# S3_Arduino.net
KiCad netlist of a schematic drawn in Altium Designer
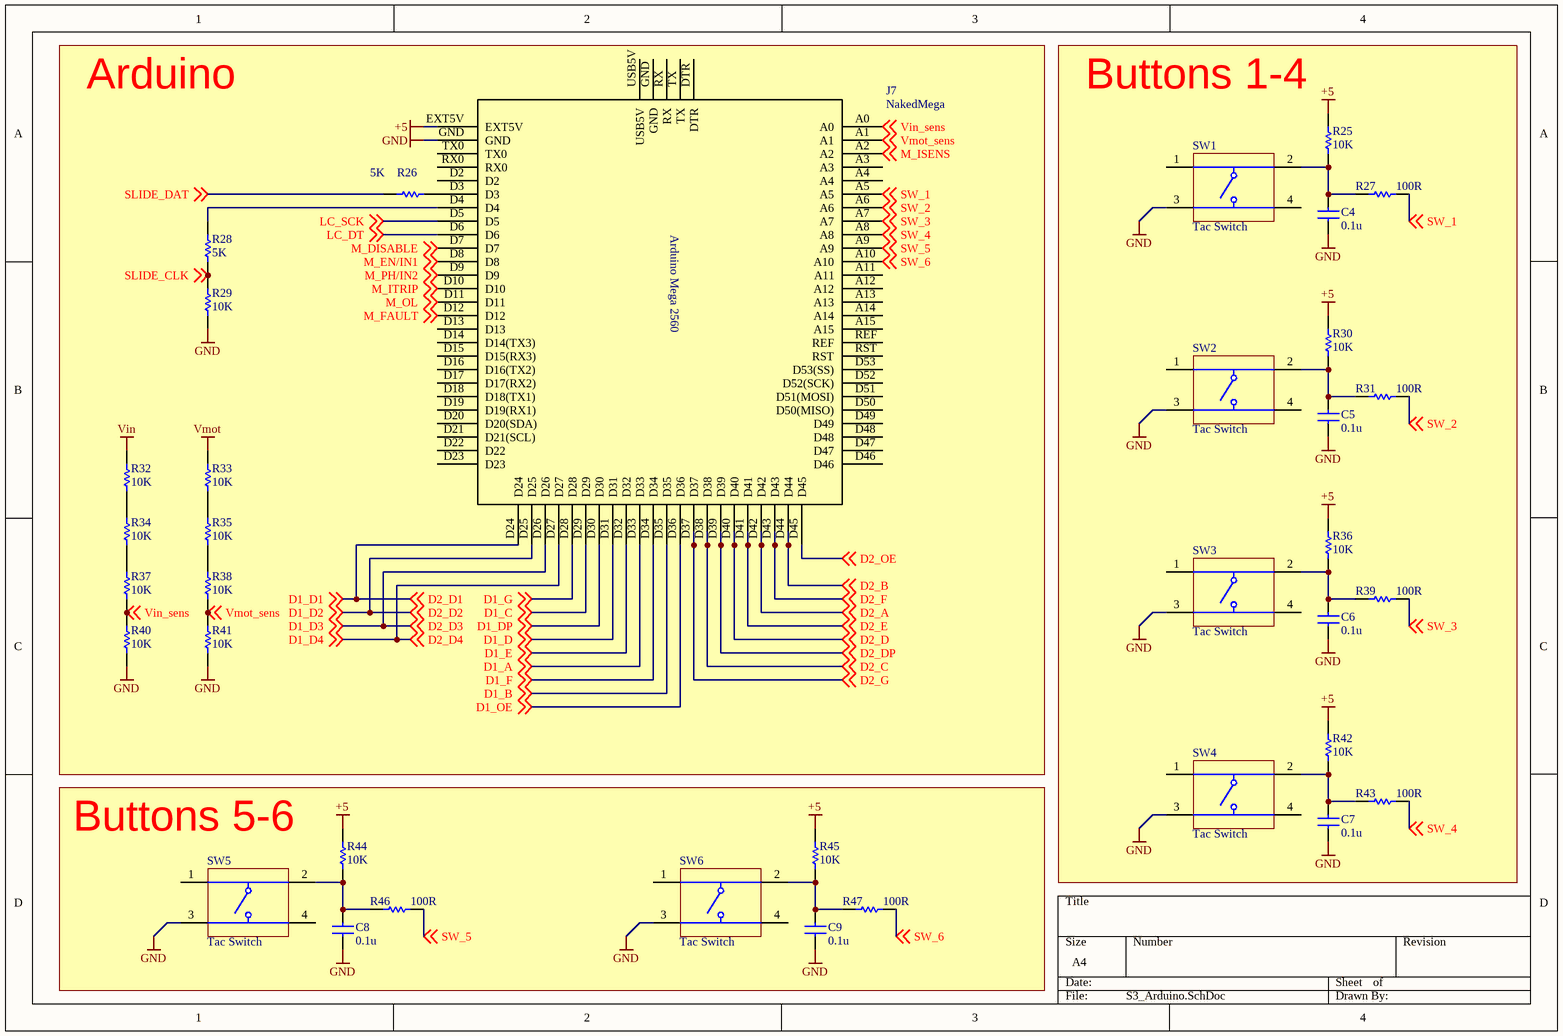
[diagram p0: S3_Arduino.SchDoc]

(export (version "E")
  (design (tool "Eeschema 10.0.6"))
  (components
    (comp (ref "C4")
      (value "0.1u")
      (footprint "Ceramic Cap 5mm")
      (libsource (lib "Res and Cap") (part "Cap"))
    )
    (comp (ref "C5")
      (value "0.1u")
      (footprint "Ceramic Cap 5mm")
      (libsource (lib "Res and Cap") (part "Cap"))
    )
    (comp (ref "C6")
      (value "0.1u")
      (footprint "Ceramic Cap 5mm")
      (libsource (lib "Res and Cap") (part "Cap"))
    )
    (comp (ref "C7")
      (value "0.1u")
      (footprint "Ceramic Cap 5mm")
      (libsource (lib "Res and Cap") (part "Cap"))
    )
    (comp (ref "C8")
      (value "0.1u")
      (footprint "Ceramic Cap 5mm")
      (libsource (lib "Res and Cap") (part "Cap"))
    )
    (comp (ref "C9")
      (value "0.1u")
      (footprint "Ceramic Cap 5mm")
      (libsource (lib "Res and Cap") (part "Cap"))
    )
    (comp (ref "J7")
      (value "NakedMega")
      (footprint "Arduino Mega")
      (libsource (lib "Custom") (part "NakedMega"))
    )
    (comp (ref "R25")
      (value "10K")
      (footprint "AXIAL-0.3-3D")
      (description "Resistor")
      (fields (field (name "Comment") "Res1") (field (name "PUBLISHER") "Altium Limited"))
      (libsource (lib "Miscellaneous Devices") (part "Res1"))
    )
    (comp (ref "R26")
      (value "5K")
      (footprint "AXIAL-0.3-3D")
      (description "Resistor")
      (fields (field (name "Comment") "Res1") (field (name "PUBLISHER") "Altium Limited"))
      (libsource (lib "Miscellaneous Devices") (part "Res1"))
    )
    (comp (ref "R27")
      (value "100R")
      (footprint "AXIAL-0.3-3D")
      (description "Resistor")
      (fields (field (name "Comment") "Res1") (field (name "PUBLISHER") "Altium Limited"))
      (libsource (lib "Miscellaneous Devices") (part "Res1"))
    )
    (comp (ref "R28")
      (value "5K")
      (footprint "AXIAL-0.3-3D")
      (description "Resistor")
      (fields (field (name "Comment") "Res1") (field (name "PUBLISHER") "Altium Limited"))
      (libsource (lib "Miscellaneous Devices") (part "Res1"))
    )
    (comp (ref "R29")
      (value "10K")
      (footprint "AXIAL-0.3-3D")
      (description "Resistor")
      (fields (field (name "Comment") "Res1") (field (name "PUBLISHER") "Altium Limited"))
      (libsource (lib "Miscellaneous Devices") (part "Res1"))
    )
    (comp (ref "R30")
      (value "10K")
      (footprint "AXIAL-0.3-3D")
      (description "Resistor")
      (fields (field (name "Comment") "Res1") (field (name "PUBLISHER") "Altium Limited"))
      (libsource (lib "Miscellaneous Devices") (part "Res1"))
    )
    (comp (ref "R31")
      (value "100R")
      (footprint "AXIAL-0.3-3D")
      (description "Resistor")
      (fields (field (name "Comment") "Res1") (field (name "PUBLISHER") "Altium Limited"))
      (libsource (lib "Miscellaneous Devices") (part "Res1"))
    )
    (comp (ref "R32")
      (value "10K")
      (footprint "AXIAL-0.3-3D")
      (description "Resistor")
      (fields (field (name "Comment") "Res1") (field (name "PUBLISHER") "Altium Limited"))
      (libsource (lib "Miscellaneous Devices") (part "Res1"))
    )
    (comp (ref "R33")
      (value "10K")
      (footprint "AXIAL-0.3-3D")
      (description "Resistor")
      (fields (field (name "Comment") "Res1") (field (name "PUBLISHER") "Altium Limited"))
      (libsource (lib "Miscellaneous Devices") (part "Res1"))
    )
    (comp (ref "R34")
      (value "10K")
      (footprint "AXIAL-0.3-3D")
      (description "Resistor")
      (fields (field (name "Comment") "Res1") (field (name "PUBLISHER") "Altium Limited"))
      (libsource (lib "Miscellaneous Devices") (part "Res1"))
    )
    (comp (ref "R35")
      (value "10K")
      (footprint "AXIAL-0.3-3D")
      (description "Resistor")
      (fields (field (name "Comment") "Res1") (field (name "PUBLISHER") "Altium Limited"))
      (libsource (lib "Miscellaneous Devices") (part "Res1"))
    )
    (comp (ref "R36")
      (value "10K")
      (footprint "AXIAL-0.3-3D")
      (description "Resistor")
      (fields (field (name "Comment") "Res1") (field (name "PUBLISHER") "Altium Limited"))
      (libsource (lib "Miscellaneous Devices") (part "Res1"))
    )
    (comp (ref "R37")
      (value "10K")
      (footprint "AXIAL-0.3-3D")
      (description "Resistor")
      (fields (field (name "Comment") "Res1") (field (name "PUBLISHER") "Altium Limited"))
      (libsource (lib "Miscellaneous Devices") (part "Res1"))
    )
    (comp (ref "R38")
      (value "10K")
      (footprint "AXIAL-0.3-3D")
      (description "Resistor")
      (fields (field (name "Comment") "Res1") (field (name "PUBLISHER") "Altium Limited"))
      (libsource (lib "Miscellaneous Devices") (part "Res1"))
    )
    (comp (ref "R39")
      (value "100R")
      (footprint "AXIAL-0.3-3D")
      (description "Resistor")
      (fields (field (name "Comment") "Res1") (field (name "PUBLISHER") "Altium Limited"))
      (libsource (lib "Miscellaneous Devices") (part "Res1"))
    )
    (comp (ref "R40")
      (value "10K")
      (footprint "AXIAL-0.3-3D")
      (description "Resistor")
      (fields (field (name "Comment") "Res1") (field (name "PUBLISHER") "Altium Limited"))
      (libsource (lib "Miscellaneous Devices") (part "Res1"))
    )
    (comp (ref "R41")
      (value "10K")
      (footprint "AXIAL-0.3-3D")
      (description "Resistor")
      (fields (field (name "Comment") "Res1") (field (name "PUBLISHER") "Altium Limited"))
      (libsource (lib "Miscellaneous Devices") (part "Res1"))
    )
    (comp (ref "R42")
      (value "10K")
      (footprint "AXIAL-0.3-3D")
      (description "Resistor")
      (fields (field (name "Comment") "Res1") (field (name "PUBLISHER") "Altium Limited"))
      (libsource (lib "Miscellaneous Devices") (part "Res1"))
    )
    (comp (ref "R43")
      (value "100R")
      (footprint "AXIAL-0.3-3D")
      (description "Resistor")
      (fields (field (name "Comment") "Res1") (field (name "PUBLISHER") "Altium Limited"))
      (libsource (lib "Miscellaneous Devices") (part "Res1"))
    )
    (comp (ref "R44")
      (value "10K")
      (footprint "AXIAL-0.3-3D")
      (description "Resistor")
      (fields (field (name "Comment") "Res1") (field (name "PUBLISHER") "Altium Limited"))
      (libsource (lib "Miscellaneous Devices") (part "Res1"))
    )
    (comp (ref "R45")
      (value "10K")
      (footprint "AXIAL-0.3-3D")
      (description "Resistor")
      (fields (field (name "Comment") "Res1") (field (name "PUBLISHER") "Altium Limited"))
      (libsource (lib "Miscellaneous Devices") (part "Res1"))
    )
    (comp (ref "R46")
      (value "100R")
      (footprint "AXIAL-0.3-3D")
      (description "Resistor")
      (fields (field (name "Comment") "Res1") (field (name "PUBLISHER") "Altium Limited"))
      (libsource (lib "Miscellaneous Devices") (part "Res1"))
    )
    (comp (ref "R47")
      (value "100R")
      (footprint "AXIAL-0.3-3D")
      (description "Resistor")
      (fields (field (name "Comment") "Res1") (field (name "PUBLISHER") "Altium Limited"))
      (libsource (lib "Miscellaneous Devices") (part "Res1"))
    )
    (comp (ref "SW1")
      (value "Tac Switch")
      (footprint "TacSwitch")
      (libsource (lib "Custom") (part "Tac Switch"))
    )
    (comp (ref "SW2")
      (value "Tac Switch")
      (footprint "TacSwitch")
      (libsource (lib "Custom") (part "Tac Switch"))
    )
    (comp (ref "SW3")
      (value "Tac Switch")
      (footprint "TacSwitch")
      (libsource (lib "Custom") (part "Tac Switch"))
    )
    (comp (ref "SW4")
      (value "Tac Switch")
      (footprint "TacSwitch")
      (libsource (lib "Custom") (part "Tac Switch"))
    )
    (comp (ref "SW5")
      (value "Tac Switch")
      (footprint "TacSwitch")
      (libsource (lib "Custom") (part "Tac Switch"))
    )
    (comp (ref "SW6")
      (value "Tac Switch")
      (footprint "TacSwitch")
      (libsource (lib "Custom") (part "Tac Switch"))
    )
  )
  (nets
    (net (code "1") (name "+5") (class "Default")
      (node (ref "J7") (pin "EXT5V") (pinfunction "EXT5V_EXT5V") (pintype "passive"))
      (node (ref "R25") (pin "1") (pinfunction "1_1") (pintype "passive"))
      (node (ref "R30") (pin "1") (pinfunction "1_1") (pintype "passive"))
      (node (ref "R36") (pin "1") (pinfunction "1_1") (pintype "passive"))
      (node (ref "R42") (pin "1") (pinfunction "1_1") (pintype "passive"))
      (node (ref "R44") (pin "1") (pinfunction "1_1") (pintype "passive"))
      (node (ref "R45") (pin "1") (pinfunction "1_1") (pintype "passive"))
    )
    (net (code "2") (name "D1_A") (class "Default")
      (node (ref "J7") (pin "D33") (pinfunction "D33_D33") (pintype "passive"))
    )
    (net (code "3") (name "D1_B") (class "Default")
      (node (ref "J7") (pin "D35") (pinfunction "D35_D35") (pintype "passive"))
    )
    (net (code "4") (name "D1_C") (class "Default")
      (node (ref "J7") (pin "D29") (pinfunction "D29_D29") (pintype "passive"))
    )
    (net (code "5") (name "D1_D") (class "Default")
      (node (ref "J7") (pin "D31") (pinfunction "D31_D31") (pintype "passive"))
    )
    (net (code "6") (name "D1_D1") (class "Default")
      (node (ref "J7") (pin "D24") (pinfunction "D24_D24") (pintype "passive"))
    )
    (net (code "7") (name "D1_D2") (class "Default")
      (node (ref "J7") (pin "D25") (pinfunction "D25_D25") (pintype "passive"))
    )
    (net (code "8") (name "D1_D3") (class "Default")
      (node (ref "J7") (pin "D26") (pinfunction "D26_D26") (pintype "passive"))
    )
    (net (code "9") (name "D1_D4") (class "Default")
      (node (ref "J7") (pin "D27") (pinfunction "D27_D27") (pintype "passive"))
    )
    (net (code "10") (name "D1_DP") (class "Default")
      (node (ref "J7") (pin "D30") (pinfunction "D30_D30") (pintype "passive"))
    )
    (net (code "11") (name "D1_E") (class "Default")
      (node (ref "J7") (pin "D32") (pinfunction "D32_D32") (pintype "passive"))
    )
    (net (code "12") (name "D1_F") (class "Default")
      (node (ref "J7") (pin "D34") (pinfunction "D34_D34") (pintype "passive"))
    )
    (net (code "13") (name "D1_G") (class "Default")
      (node (ref "J7") (pin "D28") (pinfunction "D28_D28") (pintype "passive"))
    )
    (net (code "14") (name "D1_OE") (class "Default")
      (node (ref "J7") (pin "D36") (pinfunction "D36_D36") (pintype "passive"))
    )
    (net (code "15") (name "D2_A") (class "Default")
      (node (ref "J7") (pin "D42") (pinfunction "D42_D42") (pintype "passive"))
    )
    (net (code "16") (name "D2_B") (class "Default")
      (node (ref "J7") (pin "D44") (pinfunction "D44_D44") (pintype "passive"))
    )
    (net (code "17") (name "D2_C") (class "Default")
      (node (ref "J7") (pin "D38") (pinfunction "D38_D38") (pintype "passive"))
    )
    (net (code "18") (name "D2_D") (class "Default")
      (node (ref "J7") (pin "D40") (pinfunction "D40_D40") (pintype "passive"))
    )
    (net (code "19") (name "D2_DP") (class "Default")
      (node (ref "J7") (pin "D39") (pinfunction "D39_D39") (pintype "passive"))
    )
    (net (code "20") (name "D2_E") (class "Default")
      (node (ref "J7") (pin "D41") (pinfunction "D41_D41") (pintype "passive"))
    )
    (net (code "21") (name "D2_F") (class "Default")
      (node (ref "J7") (pin "D43") (pinfunction "D43_D43") (pintype "passive"))
    )
    (net (code "22") (name "D2_G") (class "Default")
      (node (ref "J7") (pin "D37") (pinfunction "D37_D37") (pintype "passive"))
    )
    (net (code "23") (name "D2_OE") (class "Default")
      (node (ref "J7") (pin "D45") (pinfunction "D45_D45") (pintype "passive"))
    )
    (net (code "24") (name "GND") (class "Default")
      (node (ref "C4") (pin "2") (pinfunction "2_2") (pintype "passive"))
      (node (ref "C5") (pin "2") (pinfunction "2_2") (pintype "passive"))
      (node (ref "C6") (pin "2") (pinfunction "2_2") (pintype "passive"))
      (node (ref "C7") (pin "2") (pinfunction "2_2") (pintype "passive"))
      (node (ref "C8") (pin "2") (pinfunction "2_2") (pintype "passive"))
      (node (ref "C9") (pin "2") (pinfunction "2_2") (pintype "passive"))
      (node (ref "J7") (pin "GND") (pinfunction "GND_GND") (pintype "passive"))
      (node (ref "R29") (pin "2") (pinfunction "2_2") (pintype "passive"))
      (node (ref "R40") (pin "2") (pinfunction "2_2") (pintype "passive"))
      (node (ref "R41") (pin "2") (pinfunction "2_2") (pintype "passive"))
      (node (ref "SW1") (pin "3") (pinfunction "3_3") (pintype "passive"))
      (node (ref "SW2") (pin "3") (pinfunction "3_3") (pintype "passive"))
      (node (ref "SW3") (pin "3") (pinfunction "3_3") (pintype "passive"))
      (node (ref "SW4") (pin "3") (pinfunction "3_3") (pintype "passive"))
      (node (ref "SW5") (pin "3") (pinfunction "3_3") (pintype "passive"))
      (node (ref "SW6") (pin "3") (pinfunction "3_3") (pintype "passive"))
    )
    (net (code "25") (name "LC_DT") (class "Default")
      (node (ref "J7") (pin "D6") (pinfunction "D6_D6") (pintype "passive"))
    )
    (net (code "26") (name "LC_SCK") (class "Default")
      (node (ref "J7") (pin "D5") (pinfunction "D5_D5") (pintype "passive"))
    )
    (net (code "27") (name "M_DISABLE") (class "Default")
      (node (ref "J7") (pin "D7") (pinfunction "D7_D7") (pintype "passive"))
    )
    (net (code "28") (name "M_EN{slash}IN1") (class "Default")
      (node (ref "J7") (pin "D8") (pinfunction "D8_D8") (pintype "passive"))
    )
    (net (code "29") (name "M_FAULT") (class "Default")
      (node (ref "J7") (pin "D12") (pinfunction "D12_D12") (pintype "passive"))
    )
    (net (code "30") (name "M_ISENS") (class "Default")
      (node (ref "J7") (pin "A2") (pinfunction "A2_A2") (pintype "passive"))
    )
    (net (code "31") (name "M_ITRIP") (class "Default")
      (node (ref "J7") (pin "D10") (pinfunction "D10_D10") (pintype "passive"))
    )
    (net (code "32") (name "M_OL") (class "Default")
      (node (ref "J7") (pin "D11") (pinfunction "D11_D11") (pintype "passive"))
    )
    (net (code "33") (name "M_PH{slash}IN2") (class "Default")
      (node (ref "J7") (pin "D9") (pinfunction "D9_D9") (pintype "passive"))
    )
    (net (code "34") (name "Net-(C4-Pad1)") (class "Default")
      (node (ref "C4") (pin "1") (pinfunction "1_1") (pintype "passive"))
      (node (ref "R25") (pin "2") (pinfunction "2_2") (pintype "passive"))
      (node (ref "R27") (pin "1") (pinfunction "1_1") (pintype "passive"))
      (node (ref "SW1") (pin "2") (pinfunction "2_2") (pintype "passive"))
    )
    (net (code "35") (name "Net-(C5-Pad1)") (class "Default")
      (node (ref "C5") (pin "1") (pinfunction "1_1") (pintype "passive"))
      (node (ref "R30") (pin "2") (pinfunction "2_2") (pintype "passive"))
      (node (ref "R31") (pin "1") (pinfunction "1_1") (pintype "passive"))
      (node (ref "SW2") (pin "2") (pinfunction "2_2") (pintype "passive"))
    )
    (net (code "36") (name "Net-(C6-Pad1)") (class "Default")
      (node (ref "C6") (pin "1") (pinfunction "1_1") (pintype "passive"))
      (node (ref "R36") (pin "2") (pinfunction "2_2") (pintype "passive"))
      (node (ref "R39") (pin "1") (pinfunction "1_1") (pintype "passive"))
      (node (ref "SW3") (pin "2") (pinfunction "2_2") (pintype "passive"))
    )
    (net (code "37") (name "Net-(C7-Pad1)") (class "Default")
      (node (ref "C7") (pin "1") (pinfunction "1_1") (pintype "passive"))
      (node (ref "R42") (pin "2") (pinfunction "2_2") (pintype "passive"))
      (node (ref "R43") (pin "1") (pinfunction "1_1") (pintype "passive"))
      (node (ref "SW4") (pin "2") (pinfunction "2_2") (pintype "passive"))
    )
    (net (code "38") (name "Net-(C8-Pad1)") (class "Default")
      (node (ref "C8") (pin "1") (pinfunction "1_1") (pintype "passive"))
      (node (ref "R44") (pin "2") (pinfunction "2_2") (pintype "passive"))
      (node (ref "R46") (pin "1") (pinfunction "1_1") (pintype "passive"))
      (node (ref "SW5") (pin "2") (pinfunction "2_2") (pintype "passive"))
    )
    (net (code "39") (name "Net-(C9-Pad1)") (class "Default")
      (node (ref "C9") (pin "1") (pinfunction "1_1") (pintype "passive"))
      (node (ref "R45") (pin "2") (pinfunction "2_2") (pintype "passive"))
      (node (ref "R47") (pin "1") (pinfunction "1_1") (pintype "passive"))
      (node (ref "SW6") (pin "2") (pinfunction "2_2") (pintype "passive"))
    )
    (net (code "40") (name "Net-(J7-PadD3)") (class "Default")
      (node (ref "J7") (pin "D3") (pinfunction "D3_D3") (pintype "passive"))
      (node (ref "R26") (pin "2") (pinfunction "2_2") (pintype "passive"))
    )
    (net (code "41") (name "Net-(J7-PadD4)") (class "Default")
      (node (ref "J7") (pin "D4") (pinfunction "D4_D4") (pintype "passive"))
      (node (ref "R28") (pin "1") (pinfunction "1_1") (pintype "passive"))
    )
    (net (code "42") (name "Net-(R32-Pad2)") (class "Default")
      (node (ref "R32") (pin "2") (pinfunction "2_2") (pintype "passive"))
      (node (ref "R34") (pin "1") (pinfunction "1_1") (pintype "passive"))
    )
    (net (code "43") (name "Net-(R33-Pad2)") (class "Default")
      (node (ref "R33") (pin "2") (pinfunction "2_2") (pintype "passive"))
      (node (ref "R35") (pin "1") (pinfunction "1_1") (pintype "passive"))
    )
    (net (code "44") (name "Net-(R34-Pad2)") (class "Default")
      (node (ref "R34") (pin "2") (pinfunction "2_2") (pintype "passive"))
      (node (ref "R37") (pin "1") (pinfunction "1_1") (pintype "passive"))
    )
    (net (code "45") (name "Net-(R35-Pad2)") (class "Default")
      (node (ref "R35") (pin "2") (pinfunction "2_2") (pintype "passive"))
      (node (ref "R38") (pin "1") (pinfunction "1_1") (pintype "passive"))
    )
    (net (code "46") (name "SLIDE_CLK") (class "Default")
      (node (ref "R28") (pin "2") (pinfunction "2_2") (pintype "passive"))
      (node (ref "R29") (pin "1") (pinfunction "1_1") (pintype "passive"))
    )
    (net (code "47") (name "SLIDE_DAT") (class "Default")
      (node (ref "R26") (pin "1") (pinfunction "1_1") (pintype "passive"))
    )
    (net (code "48") (name "SW_1") (class "Default")
      (node (ref "J7") (pin "A5") (pinfunction "A5_A5") (pintype "passive"))
      (node (ref "R27") (pin "2") (pinfunction "2_2") (pintype "passive"))
    )
    (net (code "49") (name "SW_2") (class "Default")
      (node (ref "J7") (pin "A6") (pinfunction "A6_A6") (pintype "passive"))
      (node (ref "R31") (pin "2") (pinfunction "2_2") (pintype "passive"))
    )
    (net (code "50") (name "SW_3") (class "Default")
      (node (ref "J7") (pin "A7") (pinfunction "A7_A7") (pintype "passive"))
      (node (ref "R39") (pin "2") (pinfunction "2_2") (pintype "passive"))
    )
    (net (code "51") (name "SW_4") (class "Default")
      (node (ref "J7") (pin "A8") (pinfunction "A8_A8") (pintype "passive"))
      (node (ref "R43") (pin "2") (pinfunction "2_2") (pintype "passive"))
    )
    (net (code "52") (name "SW_5") (class "Default")
      (node (ref "J7") (pin "A9") (pinfunction "A9_A9") (pintype "passive"))
      (node (ref "R46") (pin "2") (pinfunction "2_2") (pintype "passive"))
    )
    (net (code "53") (name "SW_6") (class "Default")
      (node (ref "J7") (pin "A10") (pinfunction "A10_A10") (pintype "passive"))
      (node (ref "R47") (pin "2") (pinfunction "2_2") (pintype "passive"))
    )
    (net (code "54") (name "Vin") (class "Default")
      (node (ref "R32") (pin "1") (pinfunction "1_1") (pintype "passive"))
    )
    (net (code "55") (name "Vin_sens") (class "Default")
      (node (ref "J7") (pin "A0") (pinfunction "A0_A0") (pintype "passive"))
      (node (ref "R37") (pin "2") (pinfunction "2_2") (pintype "passive"))
      (node (ref "R40") (pin "1") (pinfunction "1_1") (pintype "passive"))
    )
    (net (code "56") (name "Vmot") (class "Default")
      (node (ref "R33") (pin "1") (pinfunction "1_1") (pintype "passive"))
    )
    (net (code "57") (name "Vmot_sens") (class "Default")
      (node (ref "J7") (pin "A1") (pinfunction "A1_A1") (pintype "passive"))
      (node (ref "R38") (pin "2") (pinfunction "2_2") (pintype "passive"))
      (node (ref "R41") (pin "1") (pinfunction "1_1") (pintype "passive"))
    )
    (net (code "58") (name "unconnected-(J7-D14(TX3)-PadD14)") (class "Default")
      (node (ref "J7") (pin "D14") (pinfunction "D14(TX3)_D14") (pintype "passive"))
    )
    (net (code "59") (name "unconnected-(J7-D15(RX3)-PadD15)") (class "Default")
      (node (ref "J7") (pin "D15") (pinfunction "D15(RX3)_D15") (pintype "passive"))
    )
    (net (code "60") (name "unconnected-(J7-D16(TX2)-PadD16)") (class "Default")
      (node (ref "J7") (pin "D16") (pinfunction "D16(TX2)_D16") (pintype "passive"))
    )
    (net (code "61") (name "unconnected-(J7-D17(RX2)-PadD17)") (class "Default")
      (node (ref "J7") (pin "D17") (pinfunction "D17(RX2)_D17") (pintype "passive"))
    )
    (net (code "62") (name "unconnected-(J7-D18(TX1)-PadD18)") (class "Default")
      (node (ref "J7") (pin "D18") (pinfunction "D18(TX1)_D18") (pintype "passive"))
    )
    (net (code "63") (name "unconnected-(J7-D19(RX1)-PadD19)") (class "Default")
      (node (ref "J7") (pin "D19") (pinfunction "D19(RX1)_D19") (pintype "passive"))
    )
    (net (code "64") (name "unconnected-(J7-D20(SDA)-PadD20)") (class "Default")
      (node (ref "J7") (pin "D20") (pinfunction "D20(SDA)_D20") (pintype "passive"))
    )
    (net (code "65") (name "unconnected-(J7-D21(SCL)-PadD21)") (class "Default")
      (node (ref "J7") (pin "D21") (pinfunction "D21(SCL)_D21") (pintype "passive"))
    )
    (net (code "66") (name "unconnected-(J7-D50(MISO)-PadD50)") (class "Default")
      (node (ref "J7") (pin "D50") (pinfunction "D50(MISO)_D50") (pintype "passive"))
    )
    (net (code "67") (name "unconnected-(J7-D51(MOSI)-PadD51)") (class "Default")
      (node (ref "J7") (pin "D51") (pinfunction "D51(MOSI)_D51") (pintype "passive"))
    )
    (net (code "68") (name "unconnected-(J7-D52(SCK)-PadD52)") (class "Default")
      (node (ref "J7") (pin "D52") (pinfunction "D52(SCK)_D52") (pintype "passive"))
    )
    (net (code "69") (name "unconnected-(J7-D53(SS)-PadD53)") (class "Default")
      (node (ref "J7") (pin "D53") (pinfunction "D53(SS)_D53") (pintype "passive"))
    )
    (net (code "70") (name "unconnected-(J7-PadA3)") (class "Default")
      (node (ref "J7") (pin "A3") (pinfunction "A3_A3") (pintype "passive"))
    )
    (net (code "71") (name "unconnected-(J7-PadA4)") (class "Default")
      (node (ref "J7") (pin "A4") (pinfunction "A4_A4") (pintype "passive"))
    )
    (net (code "72") (name "unconnected-(J7-PadA11)") (class "Default")
      (node (ref "J7") (pin "A11") (pinfunction "A11_A11") (pintype "passive"))
    )
    (net (code "73") (name "unconnected-(J7-PadA12)") (class "Default")
      (node (ref "J7") (pin "A12") (pinfunction "A12_A12") (pintype "passive"))
    )
    (net (code "74") (name "unconnected-(J7-PadA13)") (class "Default")
      (node (ref "J7") (pin "A13") (pinfunction "A13_A13") (pintype "passive"))
    )
    (net (code "75") (name "unconnected-(J7-PadA14)") (class "Default")
      (node (ref "J7") (pin "A14") (pinfunction "A14_A14") (pintype "passive"))
    )
    (net (code "76") (name "unconnected-(J7-PadA15)") (class "Default")
      (node (ref "J7") (pin "A15") (pinfunction "A15_A15") (pintype "passive"))
    )
    (net (code "77") (name "unconnected-(J7-PadD2)") (class "Default")
      (node (ref "J7") (pin "D2") (pinfunction "D2_D2") (pintype "passive"))
    )
    (net (code "78") (name "unconnected-(J7-PadD13)") (class "Default")
      (node (ref "J7") (pin "D13") (pinfunction "D13_D13") (pintype "passive"))
    )
    (net (code "79") (name "unconnected-(J7-PadD22)") (class "Default")
      (node (ref "J7") (pin "D22") (pinfunction "D22_D22") (pintype "passive"))
    )
    (net (code "80") (name "unconnected-(J7-PadD23)") (class "Default")
      (node (ref "J7") (pin "D23") (pinfunction "D23_D23") (pintype "passive"))
    )
    (net (code "81") (name "unconnected-(J7-PadD46)") (class "Default")
      (node (ref "J7") (pin "D46") (pinfunction "D46_D46") (pintype "passive"))
    )
    (net (code "82") (name "unconnected-(J7-PadD47)") (class "Default")
      (node (ref "J7") (pin "D47") (pinfunction "D47_D47") (pintype "passive"))
    )
    (net (code "83") (name "unconnected-(J7-PadD48)") (class "Default")
      (node (ref "J7") (pin "D48") (pinfunction "D48_D48") (pintype "passive"))
    )
    (net (code "84") (name "unconnected-(J7-PadD49)") (class "Default")
      (node (ref "J7") (pin "D49") (pinfunction "D49_D49") (pintype "passive"))
    )
    (net (code "85") (name "unconnected-(J7-PadDTR)") (class "Default")
      (node (ref "J7") (pin "DTR") (pinfunction "DTR_DTR") (pintype "passive"))
    )
    (net (code "86") (name "unconnected-(J7-PadGND)") (class "Default")
      (node (ref "J7") (pin "GND") (pinfunction "GND_GND") (pintype "passive"))
    )
    (net (code "87") (name "unconnected-(J7-PadREF)") (class "Default")
      (node (ref "J7") (pin "REF") (pinfunction "REF_REF") (pintype "passive"))
    )
    (net (code "88") (name "unconnected-(J7-PadRST)") (class "Default")
      (node (ref "J7") (pin "RST") (pinfunction "RST_RST") (pintype "passive"))
    )
    (net (code "89") (name "unconnected-(J7-PadRX)") (class "Default")
      (node (ref "J7") (pin "RX") (pinfunction "RX_RX") (pintype "passive"))
    )
    (net (code "90") (name "unconnected-(J7-PadRX0)") (class "Default")
      (node (ref "J7") (pin "RX0") (pinfunction "RX0_RX0") (pintype "passive"))
    )
    (net (code "91") (name "unconnected-(J7-PadTX)") (class "Default")
      (node (ref "J7") (pin "TX") (pinfunction "TX_TX") (pintype "passive"))
    )
    (net (code "92") (name "unconnected-(J7-PadTX0)") (class "Default")
      (node (ref "J7") (pin "TX0") (pinfunction "TX0_TX0") (pintype "passive"))
    )
    (net (code "93") (name "unconnected-(J7-PadUSB5V)") (class "Default")
      (node (ref "J7") (pin "USB5V") (pinfunction "USB5V_USB5V") (pintype "passive"))
    )
    (net (code "94") (name "unconnected-(SW1-Pad1)") (class "Default")
      (node (ref "SW1") (pin "1") (pinfunction "1_1") (pintype "passive"))
    )
    (net (code "95") (name "unconnected-(SW1-Pad4)") (class "Default")
      (node (ref "SW1") (pin "4") (pinfunction "4_4") (pintype "passive"))
    )
    (net (code "96") (name "unconnected-(SW2-Pad1)") (class "Default")
      (node (ref "SW2") (pin "1") (pinfunction "1_1") (pintype "passive"))
    )
    (net (code "97") (name "unconnected-(SW2-Pad4)") (class "Default")
      (node (ref "SW2") (pin "4") (pinfunction "4_4") (pintype "passive"))
    )
    (net (code "98") (name "unconnected-(SW3-Pad1)") (class "Default")
      (node (ref "SW3") (pin "1") (pinfunction "1_1") (pintype "passive"))
    )
    (net (code "99") (name "unconnected-(SW3-Pad4)") (class "Default")
      (node (ref "SW3") (pin "4") (pinfunction "4_4") (pintype "passive"))
    )
    (net (code "100") (name "unconnected-(SW4-Pad1)") (class "Default")
      (node (ref "SW4") (pin "1") (pinfunction "1_1") (pintype "passive"))
    )
    (net (code "101") (name "unconnected-(SW4-Pad4)") (class "Default")
      (node (ref "SW4") (pin "4") (pinfunction "4_4") (pintype "passive"))
    )
    (net (code "102") (name "unconnected-(SW5-Pad1)") (class "Default")
      (node (ref "SW5") (pin "1") (pinfunction "1_1") (pintype "passive"))
    )
    (net (code "103") (name "unconnected-(SW5-Pad4)") (class "Default")
      (node (ref "SW5") (pin "4") (pinfunction "4_4") (pintype "passive"))
    )
    (net (code "104") (name "unconnected-(SW6-Pad1)") (class "Default")
      (node (ref "SW6") (pin "1") (pinfunction "1_1") (pintype "passive"))
    )
    (net (code "105") (name "unconnected-(SW6-Pad4)") (class "Default")
      (node (ref "SW6") (pin "4") (pinfunction "4_4") (pintype "passive"))
    )
  )
)
